# STM32F103.net
KiCad netlist of a schematic drawn in Altium Designer
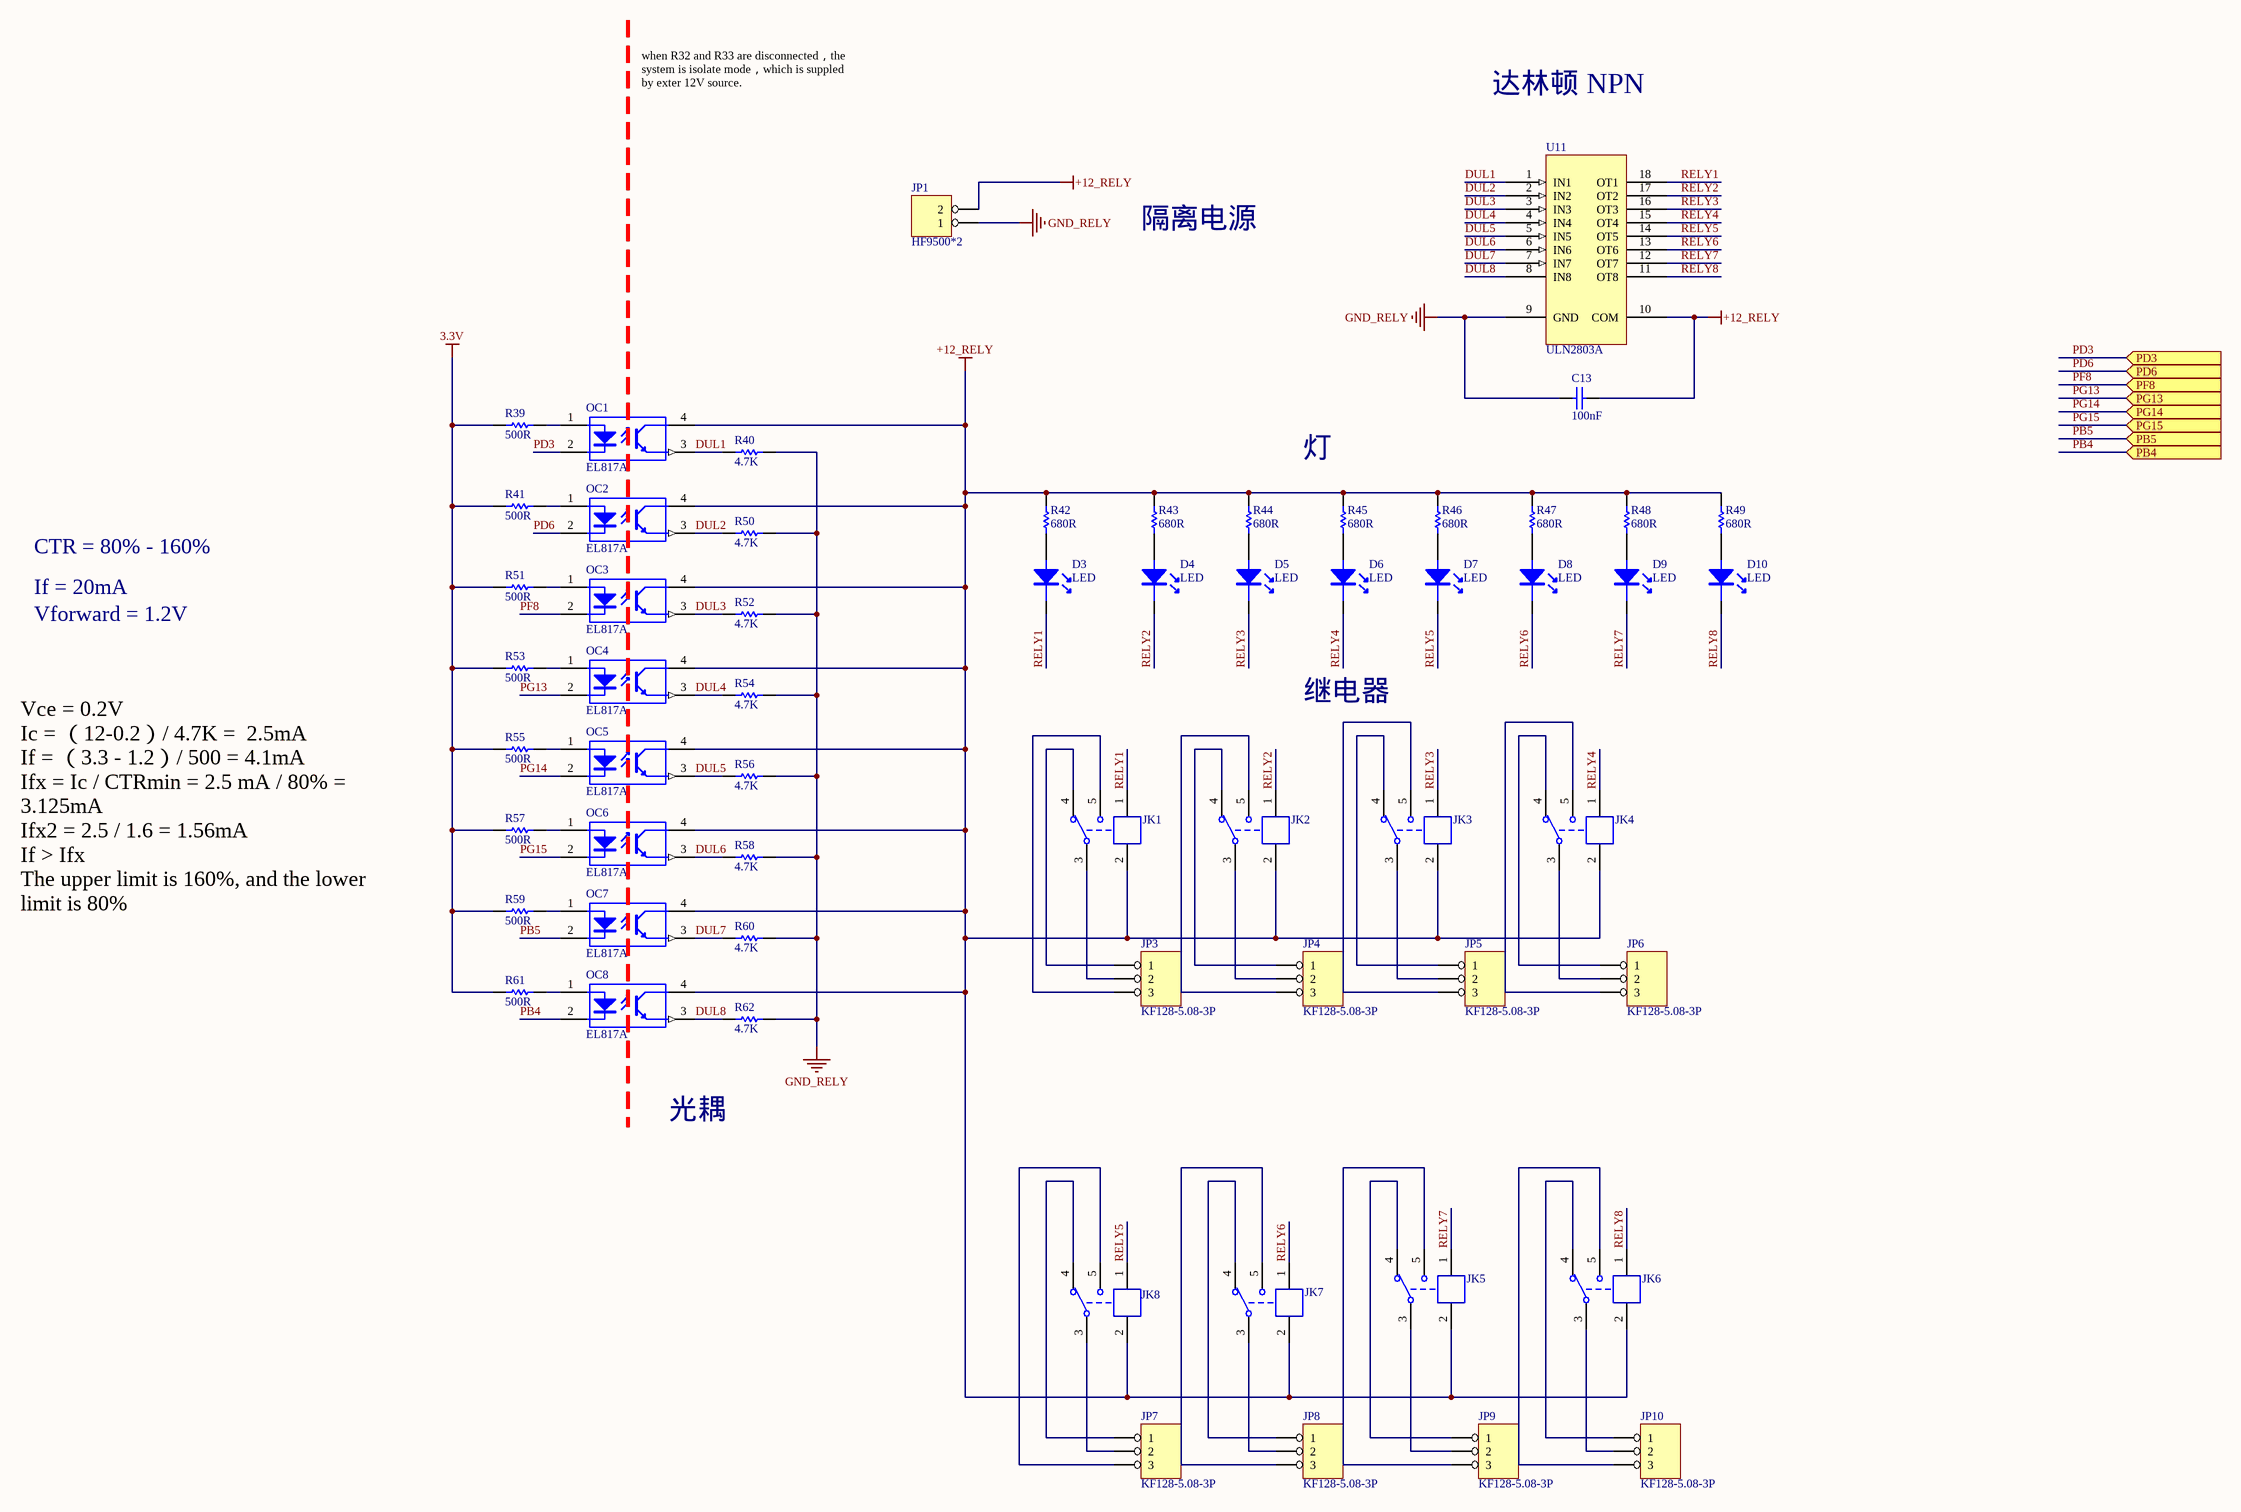
[diagram p0: STM32F103_开关量输出.SchDoc]

(export (version "E")
  (design (tool "Eeschema 10.0.6"))
  (components
    (comp (ref "C13")
      (value "100nF")
      (footprint "0603C")
      (description "Capacitor")
      (fields (field (name "PUBLISHER") "Altium Limited"))
      (libsource (lib "LJTV1.0") (part "CAP"))
    )
    (comp (ref "D3")
      (value "LED")
      (footprint "LED-0603G")
      (description "LED 发光二极管")
      (libsource (lib "LJTV1.0") (part "LED"))
    )
    (comp (ref "D4")
      (value "LED")
      (footprint "LED-0603G")
      (description "LED 发光二极管")
      (libsource (lib "LJTV1.0") (part "LED"))
    )
    (comp (ref "D5")
      (value "LED")
      (footprint "LED-0603G")
      (description "LED 发光二极管")
      (libsource (lib "LJTV1.0") (part "LED"))
    )
    (comp (ref "D6")
      (value "LED")
      (footprint "LED-0603G")
      (description "LED 发光二极管")
      (libsource (lib "LJTV1.0") (part "LED"))
    )
    (comp (ref "D7")
      (value "LED")
      (footprint "LED-0603G")
      (description "LED 发光二极管")
      (libsource (lib "LJTV1.0") (part "LED"))
    )
    (comp (ref "D8")
      (value "LED")
      (footprint "LED-0603G")
      (description "LED 发光二极管")
      (libsource (lib "LJTV1.0") (part "LED"))
    )
    (comp (ref "D9")
      (value "LED")
      (footprint "LED-0603G")
      (description "LED 发光二极管")
      (libsource (lib "LJTV1.0") (part "LED"))
    )
    (comp (ref "D10")
      (value "LED")
      (footprint "LED-0603G")
      (description "LED 发光二极管")
      (libsource (lib "LJTV1.0") (part "LED"))
    )
    (comp (ref "JK1")
      (value "SRD-05VDC-SL-C")
      (footprint "SRD-C_B")
      (description "5V一组转换")
      (libsource (lib "LJTV1.0") (part "SRD-05VDC-SL-C"))
    )
    (comp (ref "JK2")
      (value "SRD-05VDC-SL-C")
      (footprint "SRD-C_B")
      (description "5V一组转换")
      (libsource (lib "LJTV1.0") (part "SRD-05VDC-SL-C"))
    )
    (comp (ref "JK3")
      (value "SRD-05VDC-SL-C")
      (footprint "SRD-C_B")
      (description "5V一组转换")
      (libsource (lib "LJTV1.0") (part "SRD-05VDC-SL-C"))
    )
    (comp (ref "JK4")
      (value "SRD-05VDC-SL-C")
      (footprint "SRD-C_B")
      (description "5V一组转换")
      (libsource (lib "LJTV1.0") (part "SRD-05VDC-SL-C"))
    )
    (comp (ref "JK5")
      (value "SRD-05VDC-SL-C")
      (footprint "SRD-C_B")
      (description "5V一组转换")
      (libsource (lib "LJTV1.0") (part "SRD-05VDC-SL-C"))
    )
    (comp (ref "JK6")
      (value "SRD-05VDC-SL-C")
      (footprint "SRD-C_B")
      (description "5V一组转换")
      (libsource (lib "LJTV1.0") (part "SRD-05VDC-SL-C"))
    )
    (comp (ref "JK7")
      (value "SRD-05VDC-SL-C")
      (footprint "SRD-C_B")
      (description "5V一组转换")
      (libsource (lib "LJTV1.0") (part "SRD-05VDC-SL-C"))
    )
    (comp (ref "JK8")
      (value "SRD-05VDC-SL-C")
      (footprint "SRD-C_B")
      (description "5V一组转换")
      (libsource (lib "LJTV1.0") (part "SRD-05VDC-SL-C"))
    )
    (comp (ref "JP1")
      (value "HF9500*2")
      (footprint "KF128-5.08-2P")
      (libsource (lib "LJTV1.0") (part "HEADER 2"))
    )
    (comp (ref "JP3")
      (value "KF128-5.08-3P")
      (footprint "KF128-5.08-3P")
      (libsource (lib "LJTV1.0") (part "HEADER 3"))
    )
    (comp (ref "JP4")
      (value "KF128-5.08-3P")
      (footprint "KF128-5.08-3P")
      (libsource (lib "LJTV1.0") (part "HEADER 3"))
    )
    (comp (ref "JP5")
      (value "KF128-5.08-3P")
      (footprint "KF128-5.08-3P")
      (libsource (lib "LJTV1.0") (part "HEADER 3"))
    )
    (comp (ref "JP6")
      (value "KF128-5.08-3P")
      (footprint "KF128-5.08-3P")
      (libsource (lib "LJTV1.0") (part "HEADER 3"))
    )
    (comp (ref "JP7")
      (value "KF128-5.08-3P")
      (footprint "KF128-5.08-3P")
      (libsource (lib "LJTV1.0") (part "HEADER 3"))
    )
    (comp (ref "JP8")
      (value "KF128-5.08-3P")
      (footprint "KF128-5.08-3P")
      (libsource (lib "LJTV1.0") (part "HEADER 3"))
    )
    (comp (ref "JP9")
      (value "KF128-5.08-3P")
      (footprint "KF128-5.08-3P")
      (libsource (lib "LJTV1.0") (part "HEADER 3"))
    )
    (comp (ref "JP10")
      (value "KF128-5.08-3P")
      (footprint "KF128-5.08-3P")
      (libsource (lib "LJTV1.0") (part "HEADER 3"))
    )
    (comp (ref "OC1")
      (value "EL817A")
      (footprint "SMD_PC817")
      (description "线性光耦")
      (libsource (lib "LJTV1.0") (part "EL357N"))
    )
    (comp (ref "OC2")
      (value "EL817A")
      (footprint "SMD_PC817")
      (description "线性光耦")
      (libsource (lib "LJTV1.0") (part "EL357N"))
    )
    (comp (ref "OC3")
      (value "EL817A")
      (footprint "SMD_PC817")
      (description "线性光耦")
      (libsource (lib "LJTV1.0") (part "EL357N"))
    )
    (comp (ref "OC4")
      (value "EL817A")
      (footprint "SMD_PC817")
      (description "线性光耦")
      (libsource (lib "LJTV1.0") (part "EL357N"))
    )
    (comp (ref "OC5")
      (value "EL817A")
      (footprint "SMD_PC817")
      (description "线性光耦")
      (libsource (lib "LJTV1.0") (part "EL357N"))
    )
    (comp (ref "OC6")
      (value "EL817A")
      (footprint "SMD_PC817")
      (description "线性光耦")
      (libsource (lib "LJTV1.0") (part "EL357N"))
    )
    (comp (ref "OC7")
      (value "EL817A")
      (footprint "SMD_PC817")
      (description "线性光耦")
      (libsource (lib "LJTV1.0") (part "EL357N"))
    )
    (comp (ref "OC8")
      (value "EL817A")
      (footprint "SMD_PC817")
      (description "线性光耦")
      (libsource (lib "LJTV1.0") (part "EL357N"))
    )
    (comp (ref "R39")
      (value "500R")
      (footprint "0805R")
      (description "Resistor")
      (fields (field (name "PUBLISHER") "Altium Limited"))
      (libsource (lib "LJTV1.0") (part "RES"))
    )
    (comp (ref "R40")
      (value "4.7K")
      (footprint "0603R")
      (description "Resistor")
      (fields (field (name "PUBLISHER") "Altium Limited"))
      (libsource (lib "LJTV1.0") (part "RES"))
    )
    (comp (ref "R41")
      (value "500R")
      (footprint "0805R")
      (description "Resistor")
      (fields (field (name "PUBLISHER") "Altium Limited"))
      (libsource (lib "LJTV1.0") (part "RES"))
    )
    (comp (ref "R42")
      (value "680R")
      (footprint "0805R")
      (description "Resistor")
      (fields (field (name "PUBLISHER") "Altium Limited"))
      (libsource (lib "LJTV1.0") (part "RES"))
    )
    (comp (ref "R43")
      (value "680R")
      (footprint "0805R")
      (description "Resistor")
      (fields (field (name "PUBLISHER") "Altium Limited"))
      (libsource (lib "LJTV1.0") (part "RES"))
    )
    (comp (ref "R44")
      (value "680R")
      (footprint "0805R")
      (description "Resistor")
      (fields (field (name "PUBLISHER") "Altium Limited"))
      (libsource (lib "LJTV1.0") (part "RES"))
    )
    (comp (ref "R45")
      (value "680R")
      (footprint "0805R")
      (description "Resistor")
      (fields (field (name "PUBLISHER") "Altium Limited"))
      (libsource (lib "LJTV1.0") (part "RES"))
    )
    (comp (ref "R46")
      (value "680R")
      (footprint "0805R")
      (description "Resistor")
      (fields (field (name "PUBLISHER") "Altium Limited"))
      (libsource (lib "LJTV1.0") (part "RES"))
    )
    (comp (ref "R47")
      (value "680R")
      (footprint "0805R")
      (description "Resistor")
      (fields (field (name "PUBLISHER") "Altium Limited"))
      (libsource (lib "LJTV1.0") (part "RES"))
    )
    (comp (ref "R48")
      (value "680R")
      (footprint "0805R")
      (description "Resistor")
      (fields (field (name "PUBLISHER") "Altium Limited"))
      (libsource (lib "LJTV1.0") (part "RES"))
    )
    (comp (ref "R49")
      (value "680R")
      (footprint "0805R")
      (description "Resistor")
      (fields (field (name "PUBLISHER") "Altium Limited"))
      (libsource (lib "LJTV1.0") (part "RES"))
    )
    (comp (ref "R50")
      (value "4.7K")
      (footprint "0603R")
      (description "Resistor")
      (fields (field (name "PUBLISHER") "Altium Limited"))
      (libsource (lib "LJTV1.0") (part "RES"))
    )
    (comp (ref "R51")
      (value "500R")
      (footprint "0805R")
      (description "Resistor")
      (fields (field (name "PUBLISHER") "Altium Limited"))
      (libsource (lib "LJTV1.0") (part "RES"))
    )
    (comp (ref "R52")
      (value "4.7K")
      (footprint "0603R")
      (description "Resistor")
      (fields (field (name "PUBLISHER") "Altium Limited"))
      (libsource (lib "LJTV1.0") (part "RES"))
    )
    (comp (ref "R53")
      (value "500R")
      (footprint "0805R")
      (description "Resistor")
      (fields (field (name "PUBLISHER") "Altium Limited"))
      (libsource (lib "LJTV1.0") (part "RES"))
    )
    (comp (ref "R54")
      (value "4.7K")
      (footprint "0603R")
      (description "Resistor")
      (fields (field (name "PUBLISHER") "Altium Limited"))
      (libsource (lib "LJTV1.0") (part "RES"))
    )
    (comp (ref "R55")
      (value "500R")
      (footprint "0805R")
      (description "Resistor")
      (fields (field (name "PUBLISHER") "Altium Limited"))
      (libsource (lib "LJTV1.0") (part "RES"))
    )
    (comp (ref "R56")
      (value "4.7K")
      (footprint "0603R")
      (description "Resistor")
      (fields (field (name "PUBLISHER") "Altium Limited"))
      (libsource (lib "LJTV1.0") (part "RES"))
    )
    (comp (ref "R57")
      (value "500R")
      (footprint "0805R")
      (description "Resistor")
      (fields (field (name "PUBLISHER") "Altium Limited"))
      (libsource (lib "LJTV1.0") (part "RES"))
    )
    (comp (ref "R58")
      (value "4.7K")
      (footprint "0603R")
      (description "Resistor")
      (fields (field (name "PUBLISHER") "Altium Limited"))
      (libsource (lib "LJTV1.0") (part "RES"))
    )
    (comp (ref "R59")
      (value "500R")
      (footprint "0805R")
      (description "Resistor")
      (fields (field (name "PUBLISHER") "Altium Limited"))
      (libsource (lib "LJTV1.0") (part "RES"))
    )
    (comp (ref "R60")
      (value "4.7K")
      (footprint "0603R")
      (description "Resistor")
      (fields (field (name "PUBLISHER") "Altium Limited"))
      (libsource (lib "LJTV1.0") (part "RES"))
    )
    (comp (ref "R61")
      (value "500R")
      (footprint "0805R")
      (description "Resistor")
      (fields (field (name "PUBLISHER") "Altium Limited"))
      (libsource (lib "LJTV1.0") (part "RES"))
    )
    (comp (ref "R62")
      (value "4.7K")
      (footprint "0603R")
      (description "Resistor")
      (fields (field (name "PUBLISHER") "Altium Limited"))
      (libsource (lib "LJTV1.0") (part "RES"))
    )
    (comp (ref "U11")
      (value "ULN2803A")
      (footprint "SOP18 - 300mil")
      (description "8 channels Darlington")
      (libsource (lib "LJTV1.0") (part "ULN2803A"))
    )
  )
  (nets
    (net (code "1") (name "+12_RELY") (class "Default")
      (node (ref "C13") (pin "2") (pinfunction "2_2") (pintype "passive"))
      (node (ref "JK1") (pin "2") (pinfunction "2_2") (pintype "passive"))
      (node (ref "JK2") (pin "2") (pinfunction "2_2") (pintype "passive"))
      (node (ref "JK3") (pin "2") (pinfunction "2_2") (pintype "passive"))
      (node (ref "JK4") (pin "2") (pinfunction "2_2") (pintype "passive"))
      (node (ref "JK5") (pin "2") (pinfunction "2_2") (pintype "passive"))
      (node (ref "JK6") (pin "2") (pinfunction "2_2") (pintype "passive"))
      (node (ref "JK7") (pin "2") (pinfunction "2_2") (pintype "passive"))
      (node (ref "JK8") (pin "2") (pinfunction "2_2") (pintype "passive"))
      (node (ref "JP1") (pin "2") (pinfunction "2_2") (pintype "passive"))
      (node (ref "OC1") (pin "4") (pinfunction "C_4") (pintype "passive"))
      (node (ref "OC2") (pin "4") (pinfunction "C_4") (pintype "passive"))
      (node (ref "OC3") (pin "4") (pinfunction "C_4") (pintype "passive"))
      (node (ref "OC4") (pin "4") (pinfunction "C_4") (pintype "passive"))
      (node (ref "OC5") (pin "4") (pinfunction "C_4") (pintype "passive"))
      (node (ref "OC6") (pin "4") (pinfunction "C_4") (pintype "passive"))
      (node (ref "OC7") (pin "4") (pinfunction "C_4") (pintype "passive"))
      (node (ref "OC8") (pin "4") (pinfunction "C_4") (pintype "passive"))
      (node (ref "R42") (pin "1") (pinfunction "1_1") (pintype "passive"))
      (node (ref "R43") (pin "1") (pinfunction "1_1") (pintype "passive"))
      (node (ref "R44") (pin "1") (pinfunction "1_1") (pintype "passive"))
      (node (ref "R45") (pin "1") (pinfunction "1_1") (pintype "passive"))
      (node (ref "R46") (pin "1") (pinfunction "1_1") (pintype "passive"))
      (node (ref "R47") (pin "1") (pinfunction "1_1") (pintype "passive"))
      (node (ref "R48") (pin "1") (pinfunction "1_1") (pintype "passive"))
      (node (ref "R49") (pin "1") (pinfunction "1_1") (pintype "passive"))
      (node (ref "U11") (pin "10") (pinfunction "COM_10") (pintype "power_in"))
    )
    (net (code "2") (name "/DUL1") (class "Default")
      (node (ref "OC1") (pin "3") (pinfunction "E_3") (pintype "output"))
      (node (ref "R40") (pin "1") (pinfunction "1_1") (pintype "passive"))
      (node (ref "U11") (pin "1") (pinfunction "IN1_1") (pintype "input"))
    )
    (net (code "3") (name "/DUL2") (class "Default")
      (node (ref "OC2") (pin "3") (pinfunction "E_3") (pintype "output"))
      (node (ref "R50") (pin "1") (pinfunction "1_1") (pintype "passive"))
      (node (ref "U11") (pin "2") (pinfunction "IN2_2") (pintype "input"))
    )
    (net (code "4") (name "/DUL3") (class "Default")
      (node (ref "OC3") (pin "3") (pinfunction "E_3") (pintype "output"))
      (node (ref "R52") (pin "1") (pinfunction "1_1") (pintype "passive"))
      (node (ref "U11") (pin "3") (pinfunction "IN3_3") (pintype "input"))
    )
    (net (code "5") (name "/DUL4") (class "Default")
      (node (ref "OC4") (pin "3") (pinfunction "E_3") (pintype "output"))
      (node (ref "R54") (pin "1") (pinfunction "1_1") (pintype "passive"))
      (node (ref "U11") (pin "4") (pinfunction "IN4_4") (pintype "input"))
    )
    (net (code "6") (name "/DUL5") (class "Default")
      (node (ref "OC5") (pin "3") (pinfunction "E_3") (pintype "output"))
      (node (ref "R56") (pin "1") (pinfunction "1_1") (pintype "passive"))
      (node (ref "U11") (pin "5") (pinfunction "IN5_5") (pintype "input"))
    )
    (net (code "7") (name "/DUL6") (class "Default")
      (node (ref "OC6") (pin "3") (pinfunction "E_3") (pintype "output"))
      (node (ref "R58") (pin "1") (pinfunction "1_1") (pintype "passive"))
      (node (ref "U11") (pin "6") (pinfunction "IN6_6") (pintype "input"))
    )
    (net (code "8") (name "/DUL7") (class "Default")
      (node (ref "OC7") (pin "3") (pinfunction "E_3") (pintype "output"))
      (node (ref "R60") (pin "1") (pinfunction "1_1") (pintype "passive"))
      (node (ref "U11") (pin "7") (pinfunction "IN7_7") (pintype "input"))
    )
    (net (code "9") (name "/DUL8") (class "Default")
      (node (ref "OC8") (pin "3") (pinfunction "E_3") (pintype "output"))
      (node (ref "R62") (pin "1") (pinfunction "1_1") (pintype "passive"))
      (node (ref "U11") (pin "8") (pinfunction "IN8_8") (pintype "passive"))
    )
    (net (code "10") (name "/PB4") (class "Default")
      (node (ref "OC8") (pin "2") (pinfunction "K_2") (pintype "passive"))
    )
    (net (code "11") (name "/PB5") (class "Default")
      (node (ref "OC7") (pin "2") (pinfunction "K_2") (pintype "passive"))
    )
    (net (code "12") (name "/PD3") (class "Default")
      (node (ref "OC1") (pin "2") (pinfunction "K_2") (pintype "passive"))
    )
    (net (code "13") (name "/PD6") (class "Default")
      (node (ref "OC2") (pin "2") (pinfunction "K_2") (pintype "passive"))
    )
    (net (code "14") (name "/PF8") (class "Default")
      (node (ref "OC3") (pin "2") (pinfunction "K_2") (pintype "passive"))
    )
    (net (code "15") (name "/PG13") (class "Default")
      (node (ref "OC4") (pin "2") (pinfunction "K_2") (pintype "passive"))
    )
    (net (code "16") (name "/PG14") (class "Default")
      (node (ref "OC5") (pin "2") (pinfunction "K_2") (pintype "passive"))
    )
    (net (code "17") (name "/PG15") (class "Default")
      (node (ref "OC6") (pin "2") (pinfunction "K_2") (pintype "passive"))
    )
    (net (code "18") (name "/RELY1") (class "Default")
      (node (ref "D3") (pin "2") (pinfunction "K_2") (pintype "passive"))
      (node (ref "JK1") (pin "1") (pinfunction "1_1") (pintype "passive"))
      (node (ref "U11") (pin "18") (pinfunction "OT1_18") (pintype "passive"))
    )
    (net (code "19") (name "/RELY2") (class "Default")
      (node (ref "D4") (pin "2") (pinfunction "K_2") (pintype "passive"))
      (node (ref "JK2") (pin "1") (pinfunction "1_1") (pintype "passive"))
      (node (ref "U11") (pin "17") (pinfunction "OT2_17") (pintype "passive"))
    )
    (net (code "20") (name "/RELY3") (class "Default")
      (node (ref "D5") (pin "2") (pinfunction "K_2") (pintype "passive"))
      (node (ref "JK3") (pin "1") (pinfunction "1_1") (pintype "passive"))
      (node (ref "U11") (pin "16") (pinfunction "OT3_16") (pintype "passive"))
    )
    (net (code "21") (name "/RELY4") (class "Default")
      (node (ref "D6") (pin "2") (pinfunction "K_2") (pintype "passive"))
      (node (ref "JK4") (pin "1") (pinfunction "1_1") (pintype "passive"))
      (node (ref "U11") (pin "15") (pinfunction "OT4_15") (pintype "passive"))
    )
    (net (code "22") (name "/RELY5") (class "Default")
      (node (ref "D7") (pin "2") (pinfunction "K_2") (pintype "passive"))
      (node (ref "JK8") (pin "1") (pinfunction "1_1") (pintype "passive"))
      (node (ref "U11") (pin "14") (pinfunction "OT5_14") (pintype "passive"))
    )
    (net (code "23") (name "/RELY6") (class "Default")
      (node (ref "D8") (pin "2") (pinfunction "K_2") (pintype "passive"))
      (node (ref "JK7") (pin "1") (pinfunction "1_1") (pintype "passive"))
      (node (ref "U11") (pin "13") (pinfunction "OT6_13") (pintype "passive"))
    )
    (net (code "24") (name "/RELY7") (class "Default")
      (node (ref "D9") (pin "2") (pinfunction "K_2") (pintype "passive"))
      (node (ref "JK5") (pin "1") (pinfunction "1_1") (pintype "passive"))
      (node (ref "U11") (pin "12") (pinfunction "OT7_12") (pintype "passive"))
    )
    (net (code "25") (name "/RELY8") (class "Default")
      (node (ref "D10") (pin "2") (pinfunction "K_2") (pintype "passive"))
      (node (ref "JK6") (pin "1") (pinfunction "1_1") (pintype "passive"))
      (node (ref "U11") (pin "11") (pinfunction "OT8_11") (pintype "passive"))
    )
    (net (code "26") (name "3.3V") (class "Default")
      (node (ref "R39") (pin "2") (pinfunction "2_2") (pintype "passive"))
      (node (ref "R41") (pin "2") (pinfunction "2_2") (pintype "passive"))
      (node (ref "R51") (pin "2") (pinfunction "2_2") (pintype "passive"))
      (node (ref "R53") (pin "2") (pinfunction "2_2") (pintype "passive"))
      (node (ref "R55") (pin "2") (pinfunction "2_2") (pintype "passive"))
      (node (ref "R57") (pin "2") (pinfunction "2_2") (pintype "passive"))
      (node (ref "R59") (pin "2") (pinfunction "2_2") (pintype "passive"))
      (node (ref "R61") (pin "2") (pinfunction "2_2") (pintype "passive"))
    )
    (net (code "27") (name "GND_RELY") (class "Default")
      (node (ref "C13") (pin "1") (pinfunction "1_1") (pintype "passive"))
      (node (ref "JP1") (pin "1") (pinfunction "1_1") (pintype "passive"))
      (node (ref "R40") (pin "2") (pinfunction "2_2") (pintype "passive"))
      (node (ref "R50") (pin "2") (pinfunction "2_2") (pintype "passive"))
      (node (ref "R52") (pin "2") (pinfunction "2_2") (pintype "passive"))
      (node (ref "R54") (pin "2") (pinfunction "2_2") (pintype "passive"))
      (node (ref "R56") (pin "2") (pinfunction "2_2") (pintype "passive"))
      (node (ref "R58") (pin "2") (pinfunction "2_2") (pintype "passive"))
      (node (ref "R60") (pin "2") (pinfunction "2_2") (pintype "passive"))
      (node (ref "R62") (pin "2") (pinfunction "2_2") (pintype "passive"))
      (node (ref "U11") (pin "9") (pinfunction "GND_9") (pintype "power_in"))
    )
    (net (code "28") (name "Net-(D3-A)") (class "Default")
      (node (ref "D3") (pin "1") (pinfunction "A_1") (pintype "passive"))
      (node (ref "R42") (pin "2") (pinfunction "2_2") (pintype "passive"))
    )
    (net (code "29") (name "Net-(D4-A)") (class "Default")
      (node (ref "D4") (pin "1") (pinfunction "A_1") (pintype "passive"))
      (node (ref "R43") (pin "2") (pinfunction "2_2") (pintype "passive"))
    )
    (net (code "30") (name "Net-(D5-A)") (class "Default")
      (node (ref "D5") (pin "1") (pinfunction "A_1") (pintype "passive"))
      (node (ref "R44") (pin "2") (pinfunction "2_2") (pintype "passive"))
    )
    (net (code "31") (name "Net-(D6-A)") (class "Default")
      (node (ref "D6") (pin "1") (pinfunction "A_1") (pintype "passive"))
      (node (ref "R45") (pin "2") (pinfunction "2_2") (pintype "passive"))
    )
    (net (code "32") (name "Net-(D7-A)") (class "Default")
      (node (ref "D7") (pin "1") (pinfunction "A_1") (pintype "passive"))
      (node (ref "R46") (pin "2") (pinfunction "2_2") (pintype "passive"))
    )
    (net (code "33") (name "Net-(D8-A)") (class "Default")
      (node (ref "D8") (pin "1") (pinfunction "A_1") (pintype "passive"))
      (node (ref "R47") (pin "2") (pinfunction "2_2") (pintype "passive"))
    )
    (net (code "34") (name "Net-(D9-A)") (class "Default")
      (node (ref "D9") (pin "1") (pinfunction "A_1") (pintype "passive"))
      (node (ref "R48") (pin "2") (pinfunction "2_2") (pintype "passive"))
    )
    (net (code "35") (name "Net-(D10-A)") (class "Default")
      (node (ref "D10") (pin "1") (pinfunction "A_1") (pintype "passive"))
      (node (ref "R49") (pin "2") (pinfunction "2_2") (pintype "passive"))
    )
    (net (code "36") (name "Net-(JK1-Pad3)") (class "Default")
      (node (ref "JK1") (pin "3") (pinfunction "3_3") (pintype "passive"))
      (node (ref "JP3") (pin "2") (pinfunction "2_2") (pintype "passive"))
    )
    (net (code "37") (name "Net-(JK1-Pad4)") (class "Default")
      (node (ref "JK1") (pin "4") (pinfunction "4_4") (pintype "passive"))
      (node (ref "JP3") (pin "1") (pinfunction "1_1") (pintype "passive"))
    )
    (net (code "38") (name "Net-(JK1-Pad5)") (class "Default")
      (node (ref "JK1") (pin "5") (pinfunction "5_5") (pintype "passive"))
      (node (ref "JP3") (pin "3") (pinfunction "3_3") (pintype "passive"))
    )
    (net (code "39") (name "Net-(JK2-Pad3)") (class "Default")
      (node (ref "JK2") (pin "3") (pinfunction "3_3") (pintype "passive"))
      (node (ref "JP4") (pin "2") (pinfunction "2_2") (pintype "passive"))
    )
    (net (code "40") (name "Net-(JK2-Pad4)") (class "Default")
      (node (ref "JK2") (pin "4") (pinfunction "4_4") (pintype "passive"))
      (node (ref "JP4") (pin "1") (pinfunction "1_1") (pintype "passive"))
    )
    (net (code "41") (name "Net-(JK2-Pad5)") (class "Default")
      (node (ref "JK2") (pin "5") (pinfunction "5_5") (pintype "passive"))
      (node (ref "JP4") (pin "3") (pinfunction "3_3") (pintype "passive"))
    )
    (net (code "42") (name "Net-(JK3-Pad3)") (class "Default")
      (node (ref "JK3") (pin "3") (pinfunction "3_3") (pintype "passive"))
      (node (ref "JP5") (pin "2") (pinfunction "2_2") (pintype "passive"))
    )
    (net (code "43") (name "Net-(JK3-Pad4)") (class "Default")
      (node (ref "JK3") (pin "4") (pinfunction "4_4") (pintype "passive"))
      (node (ref "JP5") (pin "1") (pinfunction "1_1") (pintype "passive"))
    )
    (net (code "44") (name "Net-(JK3-Pad5)") (class "Default")
      (node (ref "JK3") (pin "5") (pinfunction "5_5") (pintype "passive"))
      (node (ref "JP5") (pin "3") (pinfunction "3_3") (pintype "passive"))
    )
    (net (code "45") (name "Net-(JK4-Pad3)") (class "Default")
      (node (ref "JK4") (pin "3") (pinfunction "3_3") (pintype "passive"))
      (node (ref "JP6") (pin "2") (pinfunction "2_2") (pintype "passive"))
    )
    (net (code "46") (name "Net-(JK4-Pad4)") (class "Default")
      (node (ref "JK4") (pin "4") (pinfunction "4_4") (pintype "passive"))
      (node (ref "JP6") (pin "1") (pinfunction "1_1") (pintype "passive"))
    )
    (net (code "47") (name "Net-(JK4-Pad5)") (class "Default")
      (node (ref "JK4") (pin "5") (pinfunction "5_5") (pintype "passive"))
      (node (ref "JP6") (pin "3") (pinfunction "3_3") (pintype "passive"))
    )
    (net (code "48") (name "Net-(JK5-Pad3)") (class "Default")
      (node (ref "JK5") (pin "3") (pinfunction "3_3") (pintype "passive"))
      (node (ref "JP9") (pin "2") (pinfunction "2_2") (pintype "passive"))
    )
    (net (code "49") (name "Net-(JK5-Pad4)") (class "Default")
      (node (ref "JK5") (pin "4") (pinfunction "4_4") (pintype "passive"))
      (node (ref "JP9") (pin "1") (pinfunction "1_1") (pintype "passive"))
    )
    (net (code "50") (name "Net-(JK5-Pad5)") (class "Default")
      (node (ref "JK5") (pin "5") (pinfunction "5_5") (pintype "passive"))
      (node (ref "JP9") (pin "3") (pinfunction "3_3") (pintype "passive"))
    )
    (net (code "51") (name "Net-(JK6-Pad3)") (class "Default")
      (node (ref "JK6") (pin "3") (pinfunction "3_3") (pintype "passive"))
      (node (ref "JP10") (pin "2") (pinfunction "2_2") (pintype "passive"))
    )
    (net (code "52") (name "Net-(JK6-Pad4)") (class "Default")
      (node (ref "JK6") (pin "4") (pinfunction "4_4") (pintype "passive"))
      (node (ref "JP10") (pin "1") (pinfunction "1_1") (pintype "passive"))
    )
    (net (code "53") (name "Net-(JK6-Pad5)") (class "Default")
      (node (ref "JK6") (pin "5") (pinfunction "5_5") (pintype "passive"))
      (node (ref "JP10") (pin "3") (pinfunction "3_3") (pintype "passive"))
    )
    (net (code "54") (name "Net-(JK7-Pad3)") (class "Default")
      (node (ref "JK7") (pin "3") (pinfunction "3_3") (pintype "passive"))
      (node (ref "JP8") (pin "2") (pinfunction "2_2") (pintype "passive"))
    )
    (net (code "55") (name "Net-(JK7-Pad4)") (class "Default")
      (node (ref "JK7") (pin "4") (pinfunction "4_4") (pintype "passive"))
      (node (ref "JP8") (pin "1") (pinfunction "1_1") (pintype "passive"))
    )
    (net (code "56") (name "Net-(JK7-Pad5)") (class "Default")
      (node (ref "JK7") (pin "5") (pinfunction "5_5") (pintype "passive"))
      (node (ref "JP8") (pin "3") (pinfunction "3_3") (pintype "passive"))
    )
    (net (code "57") (name "Net-(JK8-Pad3)") (class "Default")
      (node (ref "JK8") (pin "3") (pinfunction "3_3") (pintype "passive"))
      (node (ref "JP7") (pin "2") (pinfunction "2_2") (pintype "passive"))
    )
    (net (code "58") (name "Net-(JK8-Pad4)") (class "Default")
      (node (ref "JK8") (pin "4") (pinfunction "4_4") (pintype "passive"))
      (node (ref "JP7") (pin "1") (pinfunction "1_1") (pintype "passive"))
    )
    (net (code "59") (name "Net-(JK8-Pad5)") (class "Default")
      (node (ref "JK8") (pin "5") (pinfunction "5_5") (pintype "passive"))
      (node (ref "JP7") (pin "3") (pinfunction "3_3") (pintype "passive"))
    )
    (net (code "60") (name "Net-(OC1-A)") (class "Default")
      (node (ref "OC1") (pin "1") (pinfunction "A_1") (pintype "passive"))
      (node (ref "R39") (pin "1") (pinfunction "1_1") (pintype "passive"))
    )
    (net (code "61") (name "Net-(OC2-A)") (class "Default")
      (node (ref "OC2") (pin "1") (pinfunction "A_1") (pintype "passive"))
      (node (ref "R41") (pin "1") (pinfunction "1_1") (pintype "passive"))
    )
    (net (code "62") (name "Net-(OC3-A)") (class "Default")
      (node (ref "OC3") (pin "1") (pinfunction "A_1") (pintype "passive"))
      (node (ref "R51") (pin "1") (pinfunction "1_1") (pintype "passive"))
    )
    (net (code "63") (name "Net-(OC4-A)") (class "Default")
      (node (ref "OC4") (pin "1") (pinfunction "A_1") (pintype "passive"))
      (node (ref "R53") (pin "1") (pinfunction "1_1") (pintype "passive"))
    )
    (net (code "64") (name "Net-(OC5-A)") (class "Default")
      (node (ref "OC5") (pin "1") (pinfunction "A_1") (pintype "passive"))
      (node (ref "R55") (pin "1") (pinfunction "1_1") (pintype "passive"))
    )
    (net (code "65") (name "Net-(OC6-A)") (class "Default")
      (node (ref "OC6") (pin "1") (pinfunction "A_1") (pintype "passive"))
      (node (ref "R57") (pin "1") (pinfunction "1_1") (pintype "passive"))
    )
    (net (code "66") (name "Net-(OC7-A)") (class "Default")
      (node (ref "OC7") (pin "1") (pinfunction "A_1") (pintype "passive"))
      (node (ref "R59") (pin "1") (pinfunction "1_1") (pintype "passive"))
    )
    (net (code "67") (name "Net-(OC8-A)") (class "Default")
      (node (ref "OC8") (pin "1") (pinfunction "A_1") (pintype "passive"))
      (node (ref "R61") (pin "1") (pinfunction "1_1") (pintype "passive"))
    )
  )
)
